# Steering_Converter_1R2.net
KiCad netlist of a schematic drawn in Altium Designer
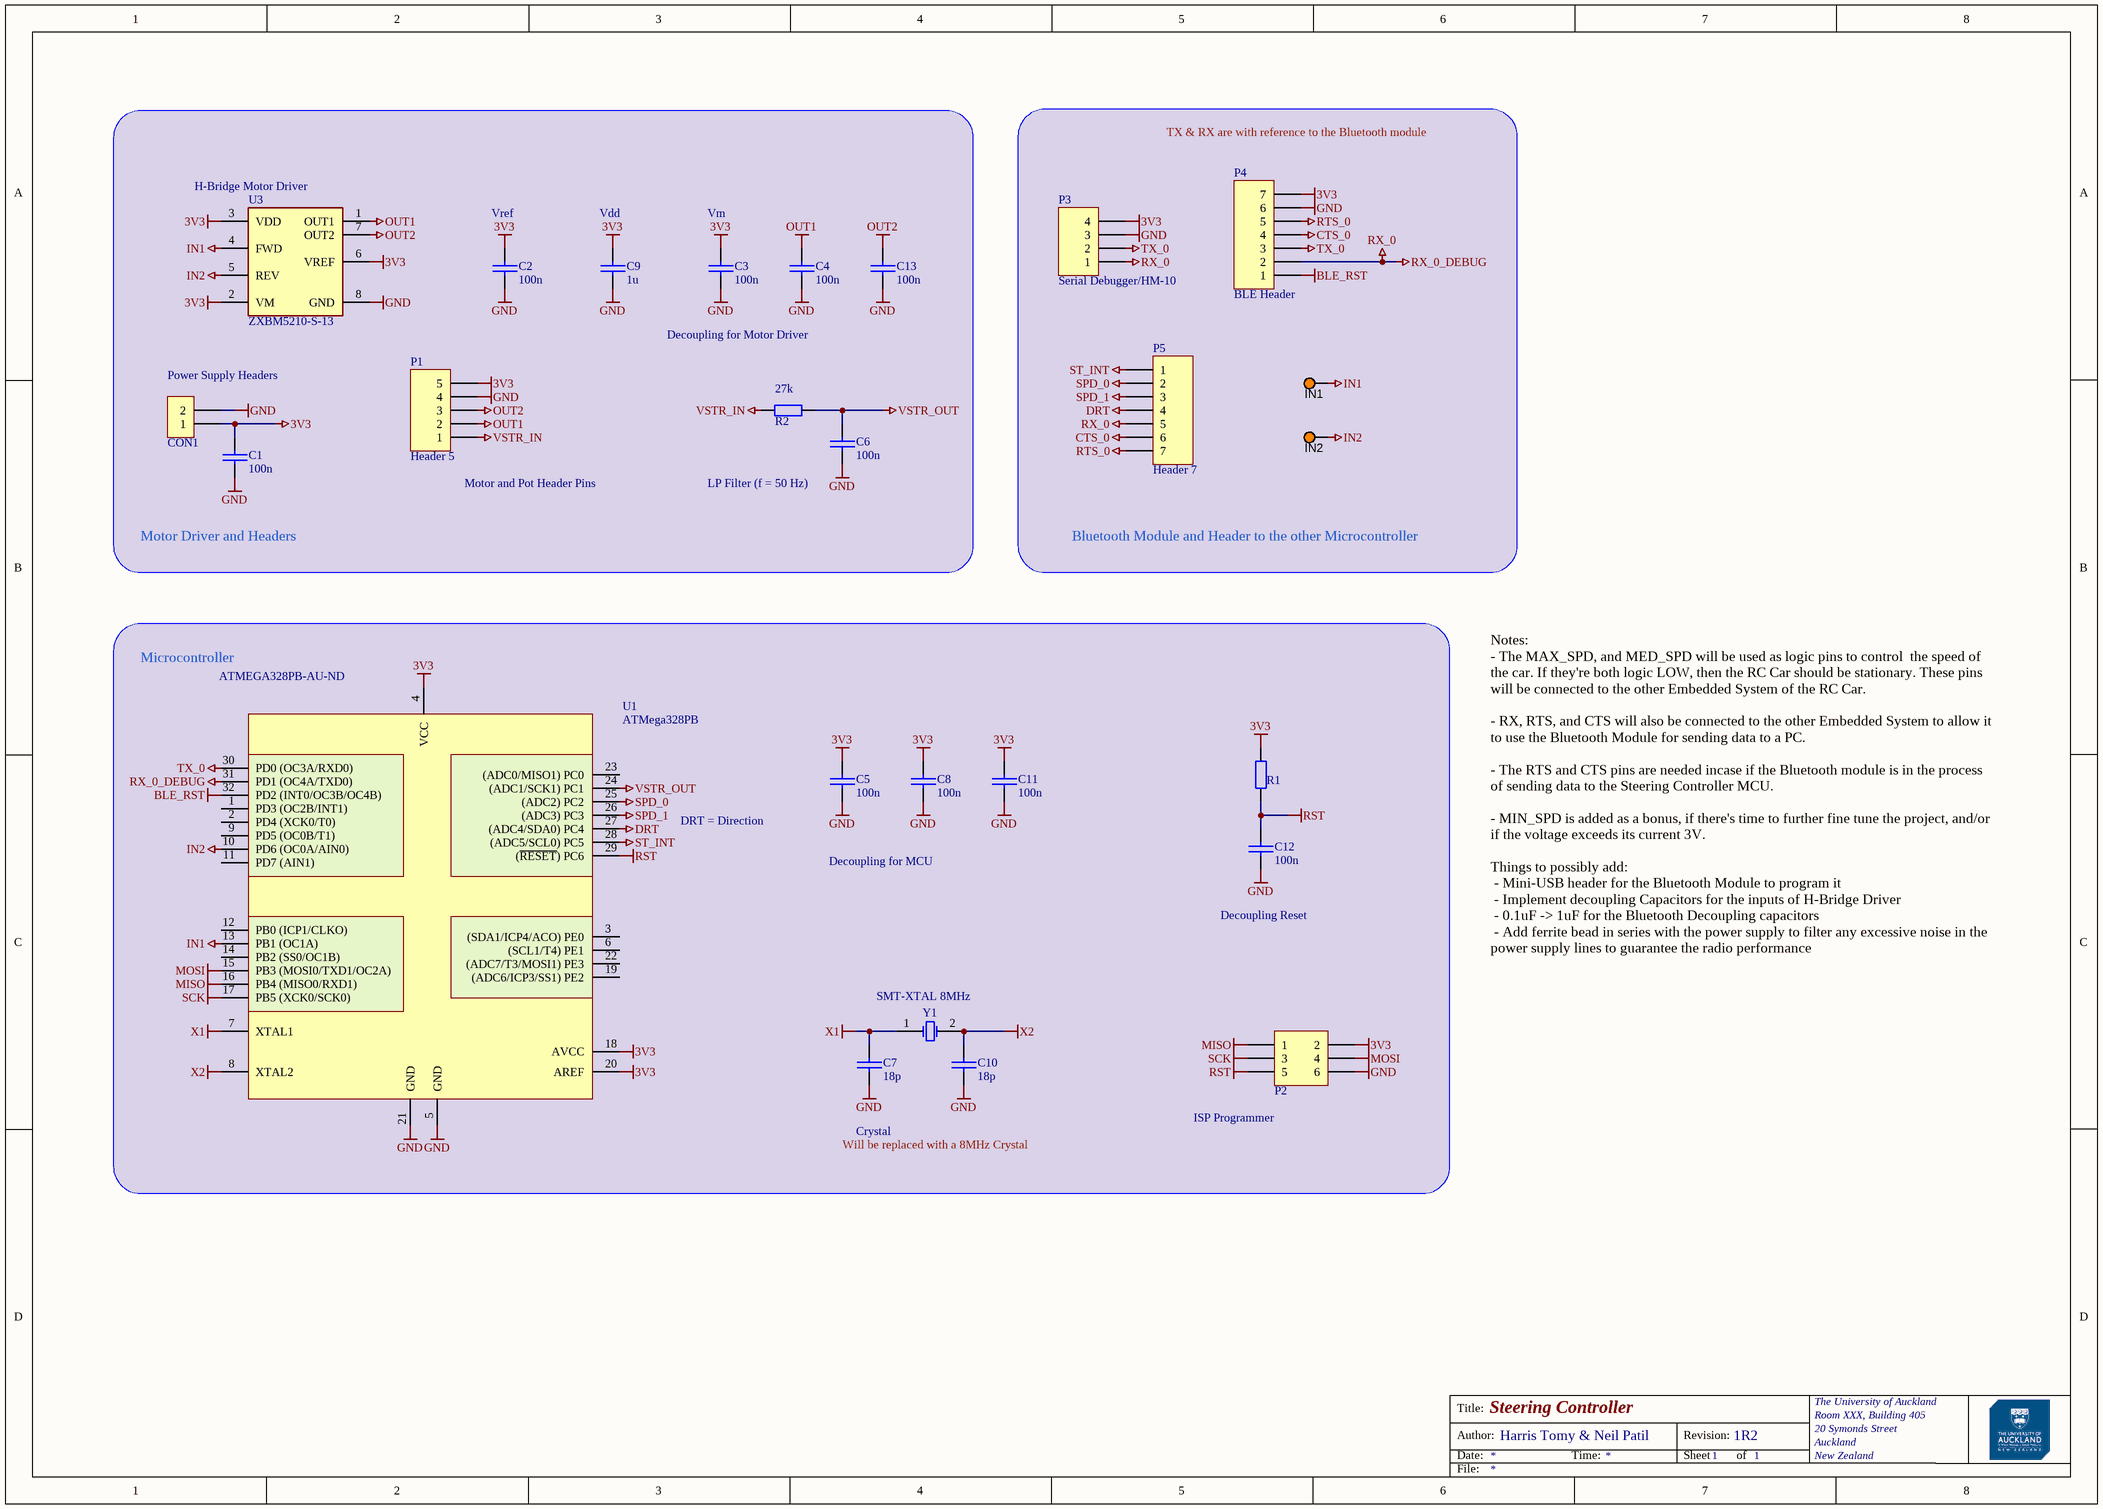
[diagram p0: Steering_Converter_1R2.SchDoc]

(export (version "E")
  (design (tool "Eeschema 10.0.6"))
  (components
    (comp (ref "C1")
      (value "100n")
      (footprint "C0805")
      (description "CCAP0805")
      (fields (field (name "MPN") "?"))
      (libsource (lib "E209_Lib") (part "CCAP0805"))
    )
    (comp (ref "C2")
      (value "100n")
      (footprint "C0805")
      (description "CCAP0805")
      (fields (field (name "MPN") "?"))
      (libsource (lib "E209_Lib") (part "CCAP0805"))
    )
    (comp (ref "C3")
      (value "100n")
      (footprint "C0805")
      (description "CCAP0805")
      (fields (field (name "MPN") "?"))
      (libsource (lib "E209_Lib") (part "CCAP0805"))
    )
    (comp (ref "C4")
      (value "100n")
      (footprint "C0805")
      (description "CCAP0805")
      (fields (field (name "MPN") "?"))
      (libsource (lib "E209_Lib") (part "CCAP0805"))
    )
    (comp (ref "C5")
      (value "100n")
      (footprint "C0805")
      (description "CCAP0805")
      (fields (field (name "MPN") "?"))
      (libsource (lib "E209_Lib") (part "CCAP0805"))
    )
    (comp (ref "C6")
      (value "100n")
      (footprint "C0805")
      (description "CCAP0805")
      (fields (field (name "MPN") "?"))
      (libsource (lib "E209_Lib") (part "CCAP0805"))
    )
    (comp (ref "C7")
      (value "18p")
      (footprint "C0805")
      (description "CCAP0805")
      (fields (field (name "MPN") "?"))
      (libsource (lib "E209_Lib") (part "CCAP0805"))
    )
    (comp (ref "C8")
      (value "100n")
      (footprint "C0805")
      (description "CCAP0805")
      (fields (field (name "MPN") "?"))
      (libsource (lib "E209_Lib") (part "CCAP0805"))
    )
    (comp (ref "C9")
      (value "1u")
      (footprint "C0805")
      (description "CCAP0805")
      (fields (field (name "MPN") "?"))
      (libsource (lib "E209_Lib") (part "CCAP0805"))
    )
    (comp (ref "C10")
      (value "18p")
      (footprint "C0805")
      (description "CCAP0805")
      (fields (field (name "MPN") "?"))
      (libsource (lib "E209_Lib") (part "CCAP0805"))
    )
    (comp (ref "C11")
      (value "100n")
      (footprint "C0805")
      (description "CCAP0805")
      (fields (field (name "MPN") "?"))
      (libsource (lib "E209_Lib") (part "CCAP0805"))
    )
    (comp (ref "C12")
      (value "100n")
      (footprint "C0805")
      (description "CCAP0805")
      (fields (field (name "MPN") "?"))
      (libsource (lib "E209_Lib") (part "CCAP0805"))
    )
    (comp (ref "C13")
      (value "100n")
      (footprint "C0805")
      (description "CCAP0805")
      (fields (field (name "MPN") "?"))
      (libsource (lib "E209_Lib") (part "CCAP0805"))
    )
    (comp (ref "CON1")
      (value "Header 2X1")
      (footprint "HDR2X1_2P54")
      (libsource (lib "CommonDevices_V1") (part "HDR2X1"))
    )
    (comp (ref "IN1")
      (value "5003")
      (footprint "TP_TH")
      (description "Test Point, Orange, 1-Pin THD, RoHS")
      (libsource (lib "EE209_Library") (part "TestPoint"))
    )
    (comp (ref "IN2")
      (value "5003")
      (footprint "TP_TH")
      (description "Test Point, Orange, 1-Pin THD, RoHS")
      (libsource (lib "EE209_Library") (part "TestPoint"))
    )
    (comp (ref "P1")
      (value "Header 5")
      (footprint "HDR1X5")
      (description "Header, 5-Pin")
      (fields (field (name "PUBLISHER") "Altium Limited"))
      (libsource (lib "Miscellaneous Connectors") (part "Header 5"))
    )
    (comp (ref "P2")
      (value "Header 3X2")
      (footprint "HDR2X3")
      (description "Header, 3-Pin, Dual row")
      (fields (field (name "PUBLISHER") "Altium Limited"))
      (libsource (lib "Miscellaneous Connectors") (part "Header 3X2"))
    )
    (comp (ref "P3")
      (value "Serial Debugger/HM-10")
      (footprint "HDR1X4")
      (description "Header, 4-Pin")
      (fields (field (name "PUBLISHER") "Altium Limited"))
      (libsource (lib "Miscellaneous Connectors") (part "Header 4"))
    )
    (comp (ref "P4")
      (value "BLE Header")
      (footprint "HDR1X7")
      (description "Header, 7-Pin")
      (fields (field (name "PUBLISHER") "Altium Limited"))
      (libsource (lib "") (part "Header 7_1"))
    )
    (comp (ref "P5")
      (value "Header 7")
      (footprint "HDR1X7")
      (description "Header, 7-Pin")
      (fields (field (name "PUBLISHER") "Altium Limited"))
      (libsource (lib "Miscellaneous Connectors") (part "Header 7"))
    )
    (comp (ref "R1")
      (value "Resistor 0805")
      (footprint "R0805")
      (description "RES0805")
      (fields (field (name "MPN") "?"))
      (libsource (lib "") (part "RES0805_1"))
    )
    (comp (ref "R2")
      (value "Resistor 0805")
      (footprint "R0805")
      (description "RES0805")
      (fields (field (name "MPN") "?"))
      (libsource (lib "E209_Lib") (part "RES0805"))
    )
    (comp (ref "U1")
      (value "ATMega328PB")
      (footprint "TQFP32")
      (description "IC MCU 8BIT 32KB FLASH 32TQFP")
      (fields (field (name "SUPPLIER PART NUMBER 1") "ATMEGA328PB-AU-ND"))
      (libsource (lib "CommonDevices_V1") (part "ATMega328PB"))
    )
    (comp (ref "U3")
      (value "IC_Diodes_ZXBM5210-S-13_eec")
      (footprint "Diodes_ZXBM5210-S-13_0")
      (description "IC MOTOR DRIVER PWM 8SOIC")
      (fields
        (field (name "PART NUMBER") "ZXBM5210-S-13")
        (field (name "VOLTAGE") "18V")
        (field (name "MANUFACTURER") "Diodes")
      )
      (libsource (lib "ZXBM5210-S-13") (part "IC_Diodes_ZXBM5210-S-13_eec"))
    )
    (comp (ref "Y1")
      (value "SMT-XTAL 8MHz")
      (footprint "HC49-US")
      (description "9C-16.000MAAJ-T crystal 16.0000MHZ 18PF SMD")
      (fields
        (field (name "MANUFACTURER") "TXC CORPORATION")
        (field (name "MANUFACTURER PART NUMBER") "9C-16.000MAAJ-T")
      )
      (libsource (lib "EE209_Library") (part "TXC9C-16_XTAL_SMT"))
    )
  )
  (nets
    (net (code "1") (name "3V3") (class "Default")
      (node (ref "C1") (pin "2") (pinfunction "2_2") (pintype "passive"))
      (node (ref "C11") (pin "2") (pinfunction "2_2") (pintype "passive"))
      (node (ref "C2") (pin "2") (pinfunction "2_2") (pintype "passive"))
      (node (ref "C3") (pin "2") (pinfunction "2_2") (pintype "passive"))
      (node (ref "C5") (pin "2") (pinfunction "2_2") (pintype "passive"))
      (node (ref "C8") (pin "2") (pinfunction "2_2") (pintype "passive"))
      (node (ref "C9") (pin "2") (pinfunction "2_2") (pintype "passive"))
      (node (ref "CON1") (pin "1") (pinfunction "1_1") (pintype "passive"))
      (node (ref "P1") (pin "5") (pinfunction "5_5") (pintype "passive"))
      (node (ref "P2") (pin "2") (pinfunction "2_2") (pintype "passive"))
      (node (ref "P3") (pin "4") (pinfunction "4_4") (pintype "passive"))
      (node (ref "P4") (pin "7") (pinfunction "7_7") (pintype "passive"))
      (node (ref "R1") (pin "2") (pinfunction "2_2") (pintype "passive"))
      (node (ref "U1") (pin "18") (pinfunction "AVCC_18") (pintype "passive"))
      (node (ref "U1") (pin "20") (pinfunction "AREF_20") (pintype "passive"))
      (node (ref "U1") (pin "4") (pinfunction "VCC_4") (pintype "passive"))
      (node (ref "U3") (pin "2") (pinfunction "VM_2") (pintype "passive"))
      (node (ref "U3") (pin "3") (pinfunction "VDD_3") (pintype "passive"))
      (node (ref "U3") (pin "6") (pinfunction "VREF_6") (pintype "passive"))
    )
    (net (code "2") (name "BLE_RST") (class "Default")
      (node (ref "P4") (pin "1") (pinfunction "1_1") (pintype "passive"))
      (node (ref "U1") (pin "32") (pinfunction "PD2_(INT0/OC3B/OC4B)_32") (pintype "passive"))
    )
    (net (code "3") (name "CTS_0") (class "Default")
      (node (ref "P4") (pin "4") (pinfunction "4_4") (pintype "passive"))
      (node (ref "P5") (pin "6") (pinfunction "6_6") (pintype "passive"))
    )
    (net (code "4") (name "DRT") (class "Default")
      (node (ref "P5") (pin "4") (pinfunction "4_4") (pintype "passive"))
      (node (ref "U1") (pin "27") (pinfunction "(ADC4/SDA0)_PC4_27") (pintype "passive"))
    )
    (net (code "5") (name "GND") (class "Default")
      (node (ref "C1") (pin "1") (pinfunction "1_1") (pintype "passive"))
      (node (ref "C10") (pin "1") (pinfunction "1_1") (pintype "passive"))
      (node (ref "C11") (pin "1") (pinfunction "1_1") (pintype "passive"))
      (node (ref "C12") (pin "1") (pinfunction "1_1") (pintype "passive"))
      (node (ref "C13") (pin "1") (pinfunction "1_1") (pintype "passive"))
      (node (ref "C2") (pin "1") (pinfunction "1_1") (pintype "passive"))
      (node (ref "C3") (pin "1") (pinfunction "1_1") (pintype "passive"))
      (node (ref "C4") (pin "1") (pinfunction "1_1") (pintype "passive"))
      (node (ref "C5") (pin "1") (pinfunction "1_1") (pintype "passive"))
      (node (ref "C6") (pin "1") (pinfunction "1_1") (pintype "passive"))
      (node (ref "C7") (pin "1") (pinfunction "1_1") (pintype "passive"))
      (node (ref "C8") (pin "1") (pinfunction "1_1") (pintype "passive"))
      (node (ref "C9") (pin "1") (pinfunction "1_1") (pintype "passive"))
      (node (ref "CON1") (pin "2") (pinfunction "2_2") (pintype "passive"))
      (node (ref "P1") (pin "4") (pinfunction "4_4") (pintype "passive"))
      (node (ref "P2") (pin "6") (pinfunction "6_6") (pintype "passive"))
      (node (ref "P3") (pin "3") (pinfunction "3_3") (pintype "passive"))
      (node (ref "P4") (pin "6") (pinfunction "6_6") (pintype "passive"))
      (node (ref "U1") (pin "21") (pinfunction "GND_21") (pintype "passive"))
      (node (ref "U1") (pin "5") (pinfunction "GND_5") (pintype "passive"))
      (node (ref "U3") (pin "8") (pinfunction "GND_8") (pintype "passive"))
    )
    (net (code "6") (name "IN1") (class "Default")
      (node (ref "IN1") (pin "1") (pinfunction "1_1") (pintype "passive"))
      (node (ref "U1") (pin "13") (pinfunction "PB1_(OC1A)_13") (pintype "passive"))
      (node (ref "U3") (pin "4") (pinfunction "FWD_4") (pintype "passive"))
    )
    (net (code "7") (name "IN2") (class "Default")
      (node (ref "IN2") (pin "1") (pinfunction "1_1") (pintype "passive"))
      (node (ref "U1") (pin "10") (pinfunction "PD6_(OC0A/AIN0)_10") (pintype "passive"))
      (node (ref "U3") (pin "5") (pinfunction "REV_5") (pintype "passive"))
    )
    (net (code "8") (name "MISO") (class "Default")
      (node (ref "P2") (pin "1") (pinfunction "1_1") (pintype "passive"))
      (node (ref "U1") (pin "16") (pinfunction "PB4_(MISO0/RXD1)_16") (pintype "passive"))
    )
    (net (code "9") (name "MOSI") (class "Default")
      (node (ref "P2") (pin "4") (pinfunction "4_4") (pintype "passive"))
      (node (ref "U1") (pin "15") (pinfunction "PB3_(MOSI0/TXD1/OC2A)_15") (pintype "passive"))
    )
    (net (code "10") (name "OUT1") (class "Default")
      (node (ref "C4") (pin "2") (pinfunction "2_2") (pintype "passive"))
      (node (ref "P1") (pin "2") (pinfunction "2_2") (pintype "passive"))
      (node (ref "U3") (pin "1") (pinfunction "OUT1_1") (pintype "passive"))
    )
    (net (code "11") (name "OUT2") (class "Default")
      (node (ref "C13") (pin "2") (pinfunction "2_2") (pintype "passive"))
      (node (ref "P1") (pin "3") (pinfunction "3_3") (pintype "passive"))
      (node (ref "U3") (pin "7") (pinfunction "OUT2_7") (pintype "passive"))
    )
    (net (code "12") (name "RST") (class "Default")
      (node (ref "C12") (pin "2") (pinfunction "2_2") (pintype "passive"))
      (node (ref "P2") (pin "5") (pinfunction "5_5") (pintype "passive"))
      (node (ref "R1") (pin "1") (pinfunction "1_1") (pintype "passive"))
      (node (ref "U1") (pin "29") (pinfunction "(~{RESET})_PC6_29") (pintype "passive"))
    )
    (net (code "13") (name "RTS_0") (class "Default")
      (node (ref "P4") (pin "5") (pinfunction "5_5") (pintype "passive"))
      (node (ref "P5") (pin "7") (pinfunction "7_7") (pintype "passive"))
    )
    (net (code "14") (name "RX_0") (class "Default")
      (node (ref "P3") (pin "1") (pinfunction "1_1") (pintype "passive"))
      (node (ref "P4") (pin "2") (pinfunction "2_2") (pintype "passive"))
      (node (ref "P5") (pin "5") (pinfunction "5_5") (pintype "passive"))
      (node (ref "U1") (pin "31") (pinfunction "PD1_(OC4A/TXD0)_31") (pintype "passive"))
    )
    (net (code "15") (name "SCK") (class "Default")
      (node (ref "P2") (pin "3") (pinfunction "3_3") (pintype "passive"))
      (node (ref "U1") (pin "17") (pinfunction "PB5_(XCK0/SCK0)_17") (pintype "passive"))
    )
    (net (code "16") (name "SPD_0") (class "Default")
      (node (ref "P5") (pin "2") (pinfunction "2_2") (pintype "passive"))
      (node (ref "U1") (pin "25") (pinfunction "(ADC2)_PC2_25") (pintype "passive"))
    )
    (net (code "17") (name "SPD_1") (class "Default")
      (node (ref "P5") (pin "3") (pinfunction "3_3") (pintype "passive"))
      (node (ref "U1") (pin "26") (pinfunction "(ADC3)_PC3_26") (pintype "passive"))
    )
    (net (code "18") (name "ST_INT") (class "Default")
      (node (ref "P5") (pin "1") (pinfunction "1_1") (pintype "passive"))
      (node (ref "U1") (pin "28") (pinfunction "(ADC5/SCL0)_PC5_28") (pintype "passive"))
    )
    (net (code "19") (name "TX_0") (class "Default")
      (node (ref "P3") (pin "2") (pinfunction "2_2") (pintype "passive"))
      (node (ref "P4") (pin "3") (pinfunction "3_3") (pintype "passive"))
      (node (ref "U1") (pin "30") (pinfunction "PD0_(OC3A/RXD0)_30") (pintype "passive"))
    )
    (net (code "20") (name "VSTR_IN") (class "Default")
      (node (ref "P1") (pin "1") (pinfunction "1_1") (pintype "passive"))
      (node (ref "R2") (pin "1") (pinfunction "1_1") (pintype "passive"))
    )
    (net (code "21") (name "VSTR_OUT") (class "Default")
      (node (ref "C6") (pin "2") (pinfunction "2_2") (pintype "passive"))
      (node (ref "R2") (pin "2") (pinfunction "2_2") (pintype "passive"))
      (node (ref "U1") (pin "24") (pinfunction "(ADC1/SCK1)_PC1_24") (pintype "passive"))
    )
    (net (code "22") (name "X1") (class "Default")
      (node (ref "C7") (pin "2") (pinfunction "2_2") (pintype "passive"))
      (node (ref "U1") (pin "7") (pinfunction "XTAL1_7") (pintype "passive"))
      (node (ref "Y1") (pin "1") (pinfunction "OSC1_1") (pintype "passive"))
    )
    (net (code "23") (name "X2") (class "Default")
      (node (ref "C10") (pin "2") (pinfunction "2_2") (pintype "passive"))
      (node (ref "U1") (pin "8") (pinfunction "XTAL2_8") (pintype "passive"))
      (node (ref "Y1") (pin "2") (pinfunction "OSC2_2") (pintype "passive"))
    )
    (net (code "24") (name "unconnected-(U1-(ADC0{slash}MISO1)_PC0-Pad23)") (class "Default")
      (node (ref "U1") (pin "23") (pinfunction "(ADC0/MISO1)_PC0_23") (pintype "passive"))
    )
    (net (code "25") (name "unconnected-(U1-(ADC6{slash}ICP3{slash}SS1)_PE2-Pad19)") (class "Default")
      (node (ref "U1") (pin "19") (pinfunction "(ADC6/ICP3/SS1)_PE2_19") (pintype "passive"))
    )
    (net (code "26") (name "unconnected-(U1-(ADC7{slash}T3{slash}MOSI1)_PE3-Pad22)") (class "Default")
      (node (ref "U1") (pin "22") (pinfunction "(ADC7/T3/MOSI1)_PE3_22") (pintype "passive"))
    )
    (net (code "27") (name "unconnected-(U1-(SCL1{slash}T4)_PE1-Pad6)") (class "Default")
      (node (ref "U1") (pin "6") (pinfunction "(SCL1/T4)_PE1_6") (pintype "passive"))
    )
    (net (code "28") (name "unconnected-(U1-(SDA1{slash}ICP4{slash}ACO)_PE0-Pad3)") (class "Default")
      (node (ref "U1") (pin "3") (pinfunction "(SDA1/ICP4/ACO)_PE0_3") (pintype "passive"))
    )
    (net (code "29") (name "unconnected-(U1-PB0_(ICP1{slash}CLKO)-Pad12)") (class "Default")
      (node (ref "U1") (pin "12") (pinfunction "PB0_(ICP1/CLKO)_12") (pintype "passive"))
    )
    (net (code "30") (name "unconnected-(U1-PB2_(SS0{slash}OC1B)-Pad14)") (class "Default")
      (node (ref "U1") (pin "14") (pinfunction "PB2_(SS0/OC1B)_14") (pintype "passive"))
    )
    (net (code "31") (name "unconnected-(U1-PD3_(OC2B{slash}INT1)-Pad1)") (class "Default")
      (node (ref "U1") (pin "1") (pinfunction "PD3_(OC2B/INT1)_1") (pintype "passive"))
    )
    (net (code "32") (name "unconnected-(U1-PD4_(XCK0{slash}T0)-Pad2)") (class "Default")
      (node (ref "U1") (pin "2") (pinfunction "PD4_(XCK0/T0)_2") (pintype "passive"))
    )
    (net (code "33") (name "unconnected-(U1-PD5_(OC0B{slash}T1)-Pad9)") (class "Default")
      (node (ref "U1") (pin "9") (pinfunction "PD5_(OC0B/T1)_9") (pintype "passive"))
    )
    (net (code "34") (name "unconnected-(U1-PD7_(AIN1)-Pad11)") (class "Default")
      (node (ref "U1") (pin "11") (pinfunction "PD7_(AIN1)_11") (pintype "passive"))
    )
  )
)
